# esp-01_breakout_v1_1.net
KiCad netlist of a schematic drawn in EAGLE
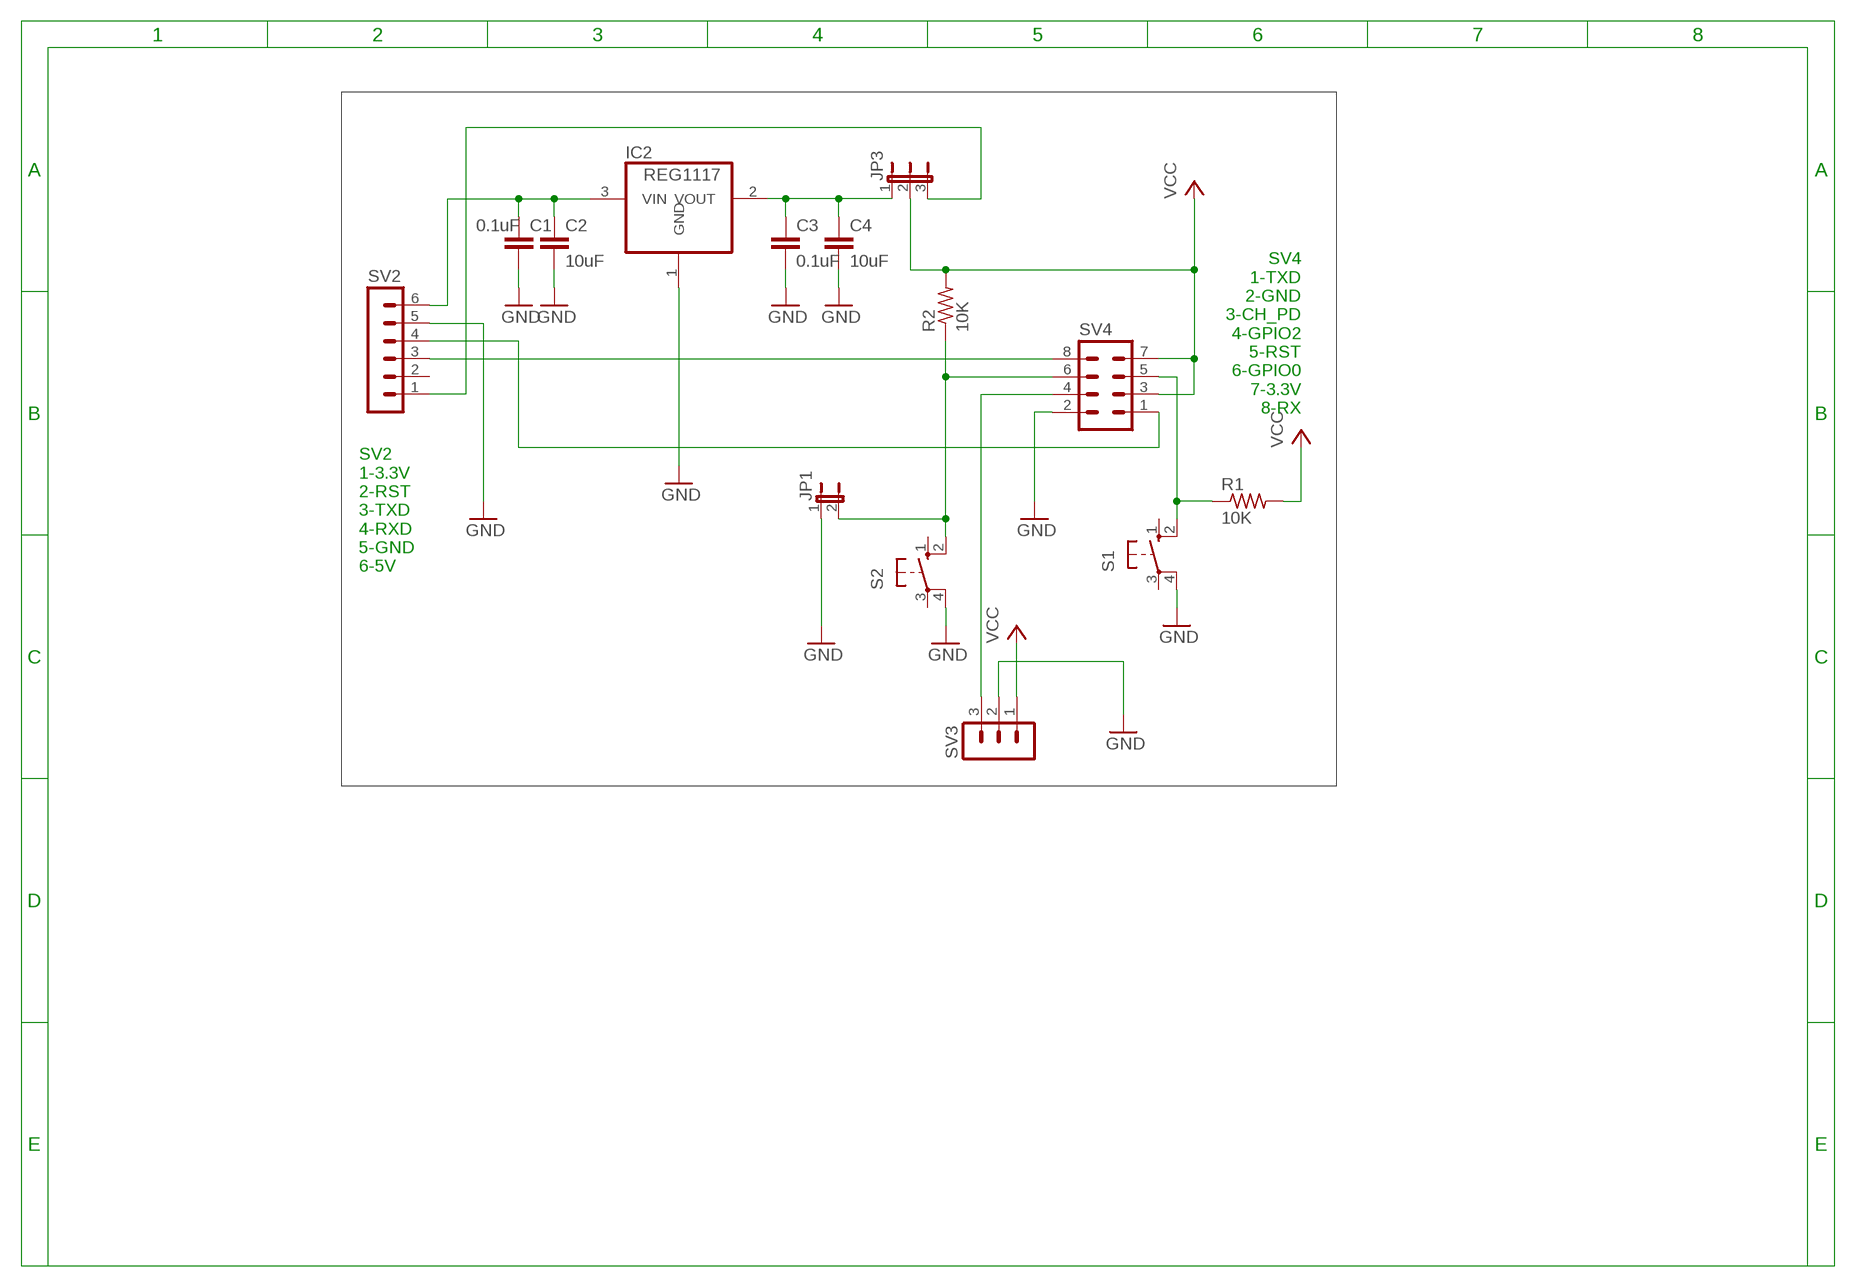
[diagram p0: schematic, sheet 1]

(export (version "E")
  (design (tool "Eeschema 10.0.6"))
  (components
    (comp (ref "C1")
      (value "0.1uF")
      (footprint "eagle-import:C025-025X050")
      (libsource (lib "eagle-import") (part "C-EU025-025X050"))
    )
    (comp (ref "C2")
      (value "10uF")
      (footprint "eagle-import:C025-025X050")
      (libsource (lib "eagle-import") (part "C-EU025-025X050"))
    )
    (comp (ref "C3")
      (value "0.1uF")
      (footprint "eagle-import:C025-025X050")
      (libsource (lib "eagle-import") (part "C-EU025-025X050"))
    )
    (comp (ref "C4")
      (value "10uF")
      (footprint "eagle-import:C025-025X050")
      (libsource (lib "eagle-import") (part "C-EU025-025X050"))
    )
    (comp (ref "IC2")
      (value "REG1117")
      (footprint "eagle-import:SOT223")
      (libsource (lib "eagle-import") (part "REG1117"))
    )
    (comp (ref "JP1")
      (value "JP1E")
      (footprint "eagle-import:JP1")
      (libsource (lib "eagle-import") (part "JP1E"))
    )
    (comp (ref "JP3")
      (value "JP2E")
      (footprint "eagle-import:JP2")
      (libsource (lib "eagle-import") (part "JP2E"))
    )
    (comp (ref "R1")
      (value "10K")
      (footprint "eagle-import:0207_7")
      (libsource (lib "eagle-import") (part "R-US_0207/7"))
    )
    (comp (ref "R2")
      (value "10K")
      (footprint "eagle-import:0207_7")
      (libsource (lib "eagle-import") (part "R-US_0207/7"))
    )
    (comp (ref "S1")
      (value "10-XX")
      (footprint "eagle-import:B3F-10XX")
      (fields (field (name "MPN") "B3F-1000"))
      (libsource (lib "eagle-import") (part "10-XX"))
    )
    (comp (ref "S2")
      (value "10-XX")
      (footprint "eagle-import:B3F-10XX")
      (fields (field (name "MPN") "B3F-1000"))
      (libsource (lib "eagle-import") (part "10-XX"))
    )
    (comp (ref "SV2")
      (value "MA06-1")
      (footprint "eagle-import:MA06-1")
      (libsource (lib "eagle-import") (part "MA06-1"))
    )
    (comp (ref "SV3")
      (value "MA03-1")
      (footprint "eagle-import:MA03-1")
      (libsource (lib "eagle-import") (part "MA03-1"))
    )
    (comp (ref "SV4")
      (value "MA04-2")
      (footprint "eagle-import:MA04-2")
      (libsource (lib "eagle-import") (part "MA04-2"))
    )
  )
  (nets
    (net (code "1") (name "GND") (class "Default")
      (node (ref "C1") (pin "2") (pinfunction "2_2") (pintype "passive"))
      (node (ref "C2") (pin "2") (pinfunction "2_2") (pintype "passive"))
      (node (ref "C3") (pin "2") (pinfunction "2_2") (pintype "passive"))
      (node (ref "C4") (pin "2") (pinfunction "2_2") (pintype "passive"))
      (node (ref "IC2") (pin "1") (pinfunction "GND_1") (pintype "power_in"))
      (node (ref "JP1") (pin "1") (pinfunction "1_1") (pintype "passive"))
      (node (ref "S1") (pin "4") (pinfunction "P1_4") (pintype "passive"))
      (node (ref "S2") (pin "4") (pinfunction "P1_4") (pintype "passive"))
      (node (ref "SV2") (pin "5") (pinfunction "5_5") (pintype "passive"))
      (node (ref "SV3") (pin "2") (pinfunction "2_2") (pintype "passive"))
      (node (ref "SV4") (pin "2") (pinfunction "2_2") (pintype "passive"))
    )
    (net (code "2") (name "Net-(IC2-VIN)") (class "Default")
      (node (ref "C1") (pin "1") (pinfunction "1_1") (pintype "passive"))
      (node (ref "C2") (pin "1") (pinfunction "1_1") (pintype "passive"))
      (node (ref "IC2") (pin "3") (pinfunction "VIN_3") (pintype "input"))
      (node (ref "SV2") (pin "6") (pinfunction "6_6") (pintype "passive"))
    )
    (net (code "3") (name "Net-(IC2-VOUT)") (class "Default")
      (node (ref "C3") (pin "1") (pinfunction "1_1") (pintype "passive"))
      (node (ref "C4") (pin "1") (pinfunction "1_1") (pintype "passive"))
      (node (ref "IC2") (pin "2") (pinfunction "VOUT_2") (pintype "output"))
      (node (ref "JP3") (pin "1") (pinfunction "1_1") (pintype "passive"))
    )
    (net (code "4") (name "Net-(JP3-Pad3)") (class "Default")
      (node (ref "JP3") (pin "3") (pinfunction "3_3") (pintype "passive"))
      (node (ref "SV2") (pin "1") (pinfunction "1_1") (pintype "passive"))
    )
    (net (code "5") (name "Net-(S1-S1)") (class "Default")
      (node (ref "R1") (pin "1") (pinfunction "1_1") (pintype "passive"))
      (node (ref "S1") (pin "2") (pinfunction "S1_2") (pintype "passive"))
      (node (ref "SV4") (pin "5") (pinfunction "5_5") (pintype "passive"))
    )
    (net (code "6") (name "Net-(S2-S1)") (class "Default")
      (node (ref "JP1") (pin "2") (pinfunction "2_2") (pintype "passive"))
      (node (ref "R2") (pin "1") (pinfunction "1_1") (pintype "passive"))
      (node (ref "S2") (pin "2") (pinfunction "S1_2") (pintype "passive"))
      (node (ref "SV4") (pin "6") (pinfunction "6_6") (pintype "passive"))
    )
    (net (code "7") (name "Net-(SV2-Pad3)") (class "Default")
      (node (ref "SV2") (pin "3") (pinfunction "3_3") (pintype "passive"))
      (node (ref "SV4") (pin "8") (pinfunction "8_8") (pintype "passive"))
    )
    (net (code "8") (name "Net-(SV2-Pad4)") (class "Default")
      (node (ref "SV2") (pin "4") (pinfunction "4_4") (pintype "passive"))
      (node (ref "SV4") (pin "1") (pinfunction "1_1") (pintype "passive"))
    )
    (net (code "9") (name "Net-(SV3-Pad3)") (class "Default")
      (node (ref "SV3") (pin "3") (pinfunction "3_3") (pintype "passive"))
      (node (ref "SV4") (pin "4") (pinfunction "4_4") (pintype "passive"))
    )
    (net (code "10") (name "VCC") (class "Default")
      (node (ref "JP3") (pin "2") (pinfunction "2_2") (pintype "passive"))
      (node (ref "R1") (pin "2") (pinfunction "2_2") (pintype "passive"))
      (node (ref "R2") (pin "2") (pinfunction "2_2") (pintype "passive"))
      (node (ref "SV3") (pin "1") (pinfunction "1_1") (pintype "passive"))
      (node (ref "SV4") (pin "3") (pinfunction "3_3") (pintype "passive"))
      (node (ref "SV4") (pin "7") (pinfunction "7_7") (pintype "passive"))
    )
    (net (code "11") (name "unconnected-(S1-P-Pad3)") (class "Default")
      (node (ref "S1") (pin "3") (pinfunction "P_3") (pintype "passive"))
    )
    (net (code "12") (name "unconnected-(S1-S-Pad1)") (class "Default")
      (node (ref "S1") (pin "1") (pinfunction "S_1") (pintype "passive"))
    )
    (net (code "13") (name "unconnected-(S2-P-Pad3)") (class "Default")
      (node (ref "S2") (pin "3") (pinfunction "P_3") (pintype "passive"))
    )
    (net (code "14") (name "unconnected-(S2-S-Pad1)") (class "Default")
      (node (ref "S2") (pin "1") (pinfunction "S_1") (pintype "passive"))
    )
    (net (code "15") (name "unconnected-(SV2-Pad2)") (class "Default")
      (node (ref "SV2") (pin "2") (pinfunction "2_2") (pintype "passive"))
    )
  )
)
